# VoltageInput.net
KiCad netlist of a schematic drawn in Altium Designer
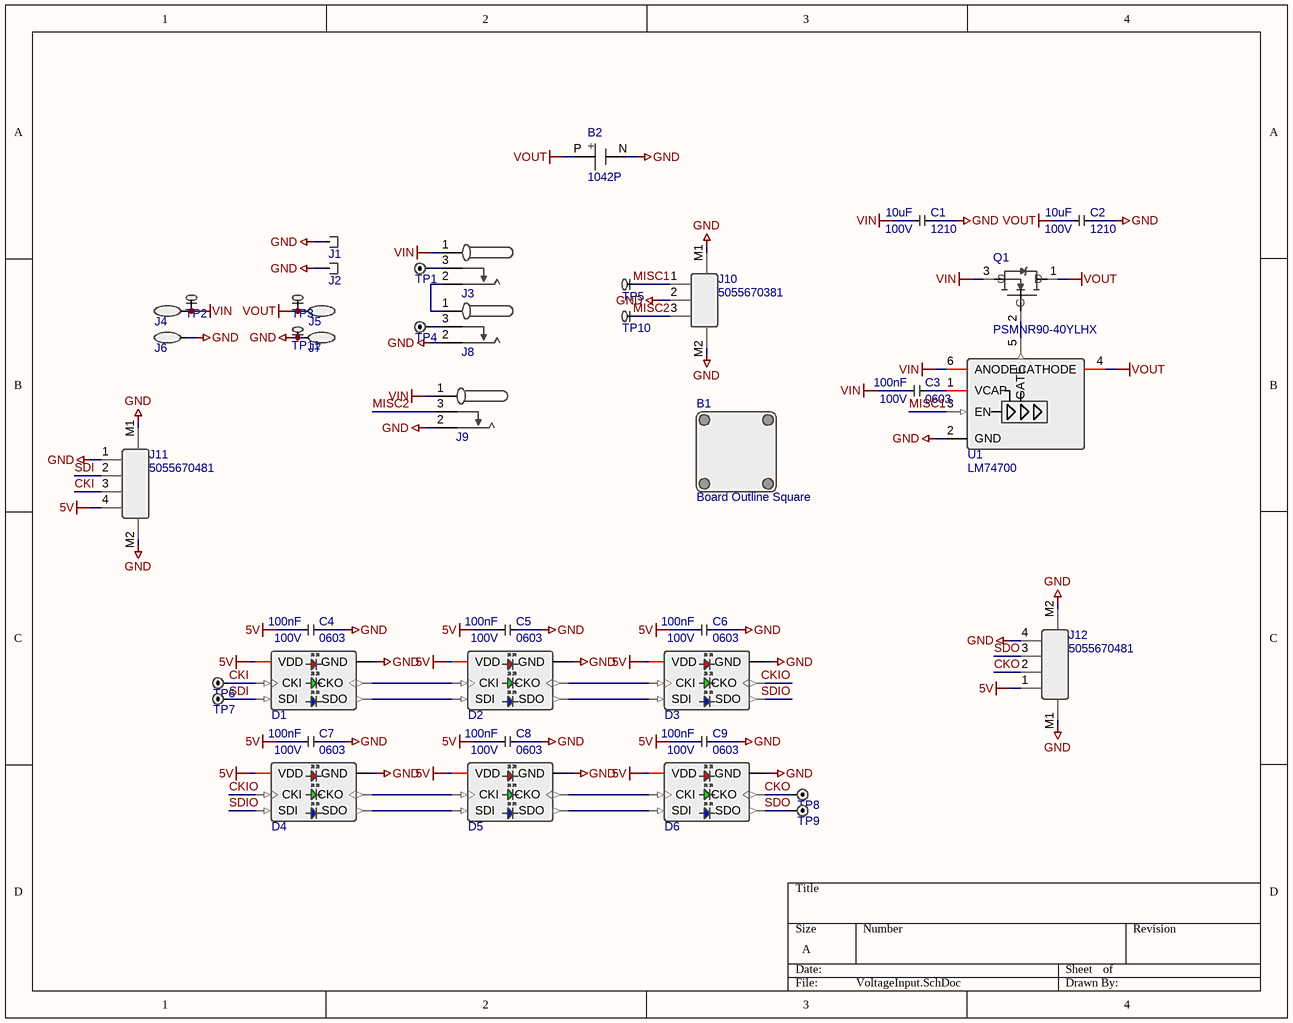
[diagram p0: VoltageInput.SchDoc]

(export (version "E")
  (design (tool "Eeschema 10.0.6"))
  (components
    (comp (ref "B1")
      (value "Board Outline Square")
      (footprint "PCB_OUTLINE_SQUARE")
      (libsource (lib "EE490") (part "Board_Outline_Square"))
    )
    (comp (ref "B2") (value "1042P") (libsource (lib "EE490") (part "Battery - Holder - Keystone 1042P")))
    (comp (ref "C1")
      (value "10uF")
      (footprint "CAPACITOR_1210(3225)_GENERIC")
      (description "10uF ±20% 100V Ceramic Capacitor X7S 1210(3225 Metric)")
      (fields
        (field (name "VOLTAGE - RATED") "100V")
        (field (name "PACKAGE/CASE IMPERIAL") "1210")
        (field (name "TOLERANCE") "20%")
        (field (name "Comment") "Capacitor - Ceramic - Generic")
      )
      (libsource (lib "EE490") (part "Capacitor - Ceramic - Generic"))
    )
    (comp (ref "C2")
      (value "10uF")
      (footprint "CAPACITOR_1210(3225)_GENERIC")
      (description "10uF ±20% 100V Ceramic Capacitor X7S 1210(3225 Metric)")
      (fields
        (field (name "VOLTAGE - RATED") "100V")
        (field (name "PACKAGE/CASE IMPERIAL") "1210")
        (field (name "TOLERANCE") "20%")
        (field (name "Comment") "Capacitor - Ceramic - Generic")
      )
      (libsource (lib "EE490") (part "Capacitor - Ceramic - Generic"))
    )
    (comp (ref "C3")
      (value "100nF")
      (footprint "CAPACITOR_0603(1608)_GENERIC")
      (description "100nF ±20% 100V Ceramic Capacitor X7R 0603(1608 Metric)")
      (fields
        (field (name "VOLTAGE - RATED") "100V")
        (field (name "PACKAGE/CASE IMPERIAL") "0603")
        (field (name "TOLERANCE") "20%")
        (field (name "Comment") "Capacitor - Ceramic - Generic")
      )
      (libsource (lib "EE490") (part "Capacitor - Ceramic - Generic"))
    )
    (comp (ref "C4")
      (value "100nF")
      (footprint "CAPACITOR_0603(1608)_GENERIC")
      (description "100nF ±20% 100V Ceramic Capacitor X7R 0603(1608 Metric)")
      (fields
        (field (name "VOLTAGE - RATED") "100V")
        (field (name "PACKAGE/CASE IMPERIAL") "0603")
        (field (name "TOLERANCE") "20%")
        (field (name "Comment") "Capacitor - Ceramic - Generic")
      )
      (libsource (lib "EE490") (part "Capacitor - Ceramic - Generic"))
    )
    (comp (ref "C5")
      (value "100nF")
      (footprint "CAPACITOR_0603(1608)_GENERIC")
      (description "100nF ±20% 100V Ceramic Capacitor X7R 0603(1608 Metric)")
      (fields
        (field (name "VOLTAGE - RATED") "100V")
        (field (name "PACKAGE/CASE IMPERIAL") "0603")
        (field (name "TOLERANCE") "20%")
        (field (name "Comment") "Capacitor - Ceramic - Generic")
      )
      (libsource (lib "EE490") (part "Capacitor - Ceramic - Generic"))
    )
    (comp (ref "C6")
      (value "100nF")
      (footprint "CAPACITOR_0603(1608)_GENERIC")
      (description "100nF ±20% 100V Ceramic Capacitor X7R 0603(1608 Metric)")
      (fields
        (field (name "VOLTAGE - RATED") "100V")
        (field (name "PACKAGE/CASE IMPERIAL") "0603")
        (field (name "TOLERANCE") "20%")
        (field (name "Comment") "Capacitor - Ceramic - Generic")
      )
      (libsource (lib "EE490") (part "Capacitor - Ceramic - Generic"))
    )
    (comp (ref "C7")
      (value "100nF")
      (footprint "CAPACITOR_0603(1608)_GENERIC")
      (description "100nF ±20% 100V Ceramic Capacitor X7R 0603(1608 Metric)")
      (fields
        (field (name "VOLTAGE - RATED") "100V")
        (field (name "PACKAGE/CASE IMPERIAL") "0603")
        (field (name "TOLERANCE") "20%")
        (field (name "Comment") "Capacitor - Ceramic - Generic")
      )
      (libsource (lib "EE490") (part "Capacitor - Ceramic - Generic"))
    )
    (comp (ref "C8")
      (value "100nF")
      (footprint "CAPACITOR_0603(1608)_GENERIC")
      (description "100nF ±20% 100V Ceramic Capacitor X7R 0603(1608 Metric)")
      (fields
        (field (name "VOLTAGE - RATED") "100V")
        (field (name "PACKAGE/CASE IMPERIAL") "0603")
        (field (name "TOLERANCE") "20%")
        (field (name "Comment") "Capacitor - Ceramic - Generic")
      )
      (libsource (lib "EE490") (part "Capacitor - Ceramic - Generic"))
    )
    (comp (ref "C9")
      (value "100nF")
      (footprint "CAPACITOR_0603(1608)_GENERIC")
      (description "100nF ±20% 100V Ceramic Capacitor X7R 0603(1608 Metric)")
      (fields
        (field (name "VOLTAGE - RATED") "100V")
        (field (name "PACKAGE/CASE IMPERIAL") "0603")
        (field (name "TOLERANCE") "20%")
        (field (name "Comment") "Capacitor - Ceramic - Generic")
      )
      (libsource (lib "EE490") (part "Capacitor - Ceramic - Generic"))
    )
    (comp (ref "D1")
      (value "APA102C")
      (footprint "5X5MM(6PIN)_JLEAD_GENERIC")
      (libsource (lib "EE490") (part "Diode - LED - Addressable - 5x5mm APA102C"))
    )
    (comp (ref "D2")
      (value "APA102C")
      (footprint "5X5MM(6PIN)_JLEAD_GENERIC")
      (libsource (lib "EE490") (part "Diode - LED - Addressable - 5x5mm APA102C"))
    )
    (comp (ref "D3")
      (value "APA102C")
      (footprint "5X5MM(6PIN)_JLEAD_GENERIC")
      (libsource (lib "EE490") (part "Diode - LED - Addressable - 5x5mm APA102C"))
    )
    (comp (ref "D4")
      (value "APA102C")
      (footprint "5X5MM(6PIN)_JLEAD_GENERIC")
      (libsource (lib "EE490") (part "Diode - LED - Addressable - 5x5mm APA102C"))
    )
    (comp (ref "D5")
      (value "APA102C")
      (footprint "5X5MM(6PIN)_JLEAD_GENERIC")
      (libsource (lib "EE490") (part "Diode - LED - Addressable - 5x5mm APA102C"))
    )
    (comp (ref "D6")
      (value "APA102C")
      (footprint "5X5MM(6PIN)_JLEAD_GENERIC")
      (libsource (lib "EE490") (part "Diode - LED - Addressable - 5x5mm APA102C"))
    )
    (comp (ref "J1")
      (value "PP45 Staple")
      (footprint "CONNECTOR_ACCESSORY_PP45-STAPLE_ANDERSON")
      (libsource (lib "EE490") (part "Connector - Accessory - Mechanical Support - Anderson PP45 Staple"))
    )
    (comp (ref "J2")
      (value "PP45 Staple")
      (footprint "CONNECTOR_ACCESSORY_PP45-STAPLE_ANDERSON")
      (libsource (lib "EE490") (part "Connector - Accessory - Mechanical Support - Anderson PP45 Staple"))
    )
    (comp (ref "J3")
      (value "839-1508-ND")
      (footprint "CONNECTOR_BARREL_TENSILITY_839-1508-ND")
      (libsource (lib "EE490") (part "Connector - Barrel - 3.5mmx1.1mm - Tensility 839-1508-ND"))
    )
    (comp (ref "J4")
      (value "PP45")
      (footprint "CONNECTOR_BTOC_PP45_ANDERSON")
      (libsource (lib "EE490") (part "Connector - Modular - 1P - Anderson PP45"))
    )
    (comp (ref "J5")
      (value "PP45")
      (footprint "CONNECTOR_BTOC_PP45_ANDERSON")
      (libsource (lib "EE490") (part "Connector - Modular - 1P - Anderson PP45"))
    )
    (comp (ref "J6")
      (value "PP45")
      (footprint "CONNECTOR_BTOC_PP45_ANDERSON")
      (libsource (lib "EE490") (part "Connector - Modular - 1P - Anderson PP45"))
    )
    (comp (ref "J7")
      (value "PP45")
      (footprint "CONNECTOR_BTOC_PP45_ANDERSON")
      (libsource (lib "EE490") (part "Connector - Modular - 1P - Anderson PP45"))
    )
    (comp (ref "J8")
      (value "839-1508-ND")
      (footprint "CONNECTOR_BARREL_TENSILITY_839-1508-ND")
      (libsource (lib "EE490") (part "Connector - Barrel - 3.5mmx1.1mm - Tensility 839-1508-ND"))
    )
    (comp (ref "J9")
      (value "839-1508-ND")
      (footprint "CONNECTOR_BARREL_TENSILITY_839-1508-ND")
      (libsource (lib "EE490") (part "Connector - Barrel - 3.5mmx1.1mm - Tensility 839-1508-ND"))
    )
    (comp (ref "J10")
      (value "Connector - Header - 3P 2M - Generic")
      (footprint "CONNECTOR_HEADER_MOLEX_5055670381")
      (description "Connector Header 3 Pin 1.25mm Pitch Mating 50V 2.4A Rated 5 Walls Shrouded SMT Molex 5055670381")
      (fields (field (name "MANUFACTURER PART NUMBER 1") "5055670381"))
      (libsource (lib "EE490") (part "Connector - Header - 3P 2M - Generic"))
    )
    (comp (ref "J11")
      (value "Connector - Header - 4P 2M - Generic")
      (footprint "CONNECTOR_HEADER_MOLEX_5055670481")
      (description "Connector Header 4 Pin 1.25mm Pitch Mating 50V 2.4A Rated 6 Walls Shrouded SMT Molex 5055670481")
      (fields (field (name "MANUFACTURER PART NUMBER 1") "5055670481"))
      (libsource (lib "EE490") (part "Connector - Header - 4P 2M - Generic"))
    )
    (comp (ref "J12")
      (value "Connector - Header - 4P 2M - Generic")
      (footprint "CONNECTOR_HEADER_MOLEX_5055670481")
      (description "Connector Header 4 Pin 1.25mm Pitch Mating 50V 2.4A Rated 6 Walls Shrouded SMT Molex 5055670481")
      (fields (field (name "MANUFACTURER PART NUMBER 1") "5055670481"))
      (libsource (lib "EE490") (part "Connector - Header - 4P 2M - Generic"))
    )
    (comp (ref "Q1")
      (value "PSMNR90-40YLHX")
      (footprint "SOT1023(LFPAK56E)_NEXPERIA")
      (libsource (lib "EE490") (part "MOSFET - N Channel - Nexperia PSMNR90-40YLHX"))
    )
    (comp (ref "TP1")
      (value "Test Point - THT")
      (footprint "TESTPOINT_THT_OCTAGON")
      (libsource (lib "EE490") (part "Test Point - THT"))
    )
    (comp (ref "TP2")
      (value "519XTR")
      (footprint "TESTPOINT_LOOP_SMD_KEYSTONE_519X")
      (libsource (lib "EE490") (part "Test Point - SMT - Loop - Keystone 519X"))
    )
    (comp (ref "TP3")
      (value "519XTR")
      (footprint "TESTPOINT_LOOP_SMD_KEYSTONE_519X")
      (libsource (lib "EE490") (part "Test Point - SMT - Loop - Keystone 519X"))
    )
    (comp (ref "TP4")
      (value "Test Point - THT")
      (footprint "TESTPOINT_THT_OCTAGON")
      (libsource (lib "EE490") (part "Test Point - THT"))
    )
    (comp (ref "TP5")
      (value "519XTR")
      (footprint "TESTPOINT_LOOP_SMD_KEYSTONE_519X")
      (libsource (lib "EE490") (part "Test Point - SMT - Loop - Keystone 519X"))
    )
    (comp (ref "TP6")
      (value "Test Point - THT")
      (footprint "TESTPOINT_THT_OCTAGON")
      (libsource (lib "EE490") (part "Test Point - THT"))
    )
    (comp (ref "TP7")
      (value "Test Point - THT")
      (footprint "TESTPOINT_THT_OCTAGON")
      (libsource (lib "EE490") (part "Test Point - THT"))
    )
    (comp (ref "TP8")
      (value "Test Point - THT")
      (footprint "TESTPOINT_THT_OCTAGON")
      (libsource (lib "EE490") (part "Test Point - THT"))
    )
    (comp (ref "TP9")
      (value "Test Point - THT")
      (footprint "TESTPOINT_THT_OCTAGON")
      (libsource (lib "EE490") (part "Test Point - THT"))
    )
    (comp (ref "TP10")
      (value "519XTR")
      (footprint "TESTPOINT_LOOP_SMD_KEYSTONE_519X")
      (libsource (lib "EE490") (part "Test Point - SMT - Loop - Keystone 519X"))
    )
    (comp (ref "TP11")
      (value "519XTR")
      (footprint "TESTPOINT_LOOP_SMD_KEYSTONE_519X")
      (libsource (lib "EE490") (part "Test Point - SMT - Loop - Keystone 519X"))
    )
    (comp (ref "U1")
      (value "LM74700")
      (footprint "SOT23-6(DBV0006A)_TI")
      (libsource (lib "EE490") (part "IC - Power Management - Ideal Diode Controller - TI LM74700"))
    )
  )
  (nets
    (net (code "1") (name "/CKI") (class "Default")
      (node (ref "D1") (pin "2") (pinfunction "CKI_2") (pintype "input"))
      (node (ref "J11") (pin "3") (pinfunction "0_3") (pintype "passive"))
      (node (ref "TP6") (pin "1") (pinfunction "1_1") (pintype "passive"))
    )
    (net (code "2") (name "/CKIO") (class "Default")
      (node (ref "D3") (pin "5") (pinfunction "CKO_5") (pintype "output"))
      (node (ref "D4") (pin "2") (pinfunction "CKI_2") (pintype "input"))
    )
    (net (code "3") (name "/CKO") (class "Default")
      (node (ref "D6") (pin "5") (pinfunction "CKO_5") (pintype "output"))
      (node (ref "J12") (pin "2") (pinfunction "0_2") (pintype "passive"))
      (node (ref "TP8") (pin "1") (pinfunction "1_1") (pintype "passive"))
    )
    (net (code "4") (name "/MISC1") (class "Default")
      (node (ref "J10") (pin "1") (pinfunction "0_1") (pintype "passive"))
      (node (ref "TP5") (pin "1") (pinfunction "1_1") (pintype "passive"))
      (node (ref "U1") (pin "3") (pinfunction "EN_3") (pintype "input"))
    )
    (net (code "5") (name "/MISC2") (class "Default")
      (node (ref "J10") (pin "3") (pinfunction "0_3") (pintype "passive"))
      (node (ref "J9") (pin "3") (pinfunction "3_3") (pintype "passive"))
      (node (ref "TP10") (pin "1") (pinfunction "1_1") (pintype "passive"))
    )
    (net (code "6") (name "/SDI") (class "Default")
      (node (ref "D1") (pin "1") (pinfunction "SDI_1") (pintype "input"))
      (node (ref "J11") (pin "2") (pinfunction "0_2") (pintype "passive"))
      (node (ref "TP7") (pin "1") (pinfunction "1_1") (pintype "passive"))
    )
    (net (code "7") (name "/SDIO") (class "Default")
      (node (ref "D3") (pin "6") (pinfunction "SDO_6") (pintype "output"))
      (node (ref "D4") (pin "1") (pinfunction "SDI_1") (pintype "input"))
    )
    (net (code "8") (name "/SDO") (class "Default")
      (node (ref "D6") (pin "6") (pinfunction "SDO_6") (pintype "output"))
      (node (ref "J12") (pin "3") (pinfunction "0_3") (pintype "passive"))
      (node (ref "TP9") (pin "1") (pinfunction "1_1") (pintype "passive"))
    )
    (net (code "9") (name "5V") (class "Default")
      (node (ref "C4") (pin "1") (pinfunction "1_1") (pintype "passive"))
      (node (ref "C5") (pin "1") (pinfunction "1_1") (pintype "passive"))
      (node (ref "C6") (pin "1") (pinfunction "1_1") (pintype "passive"))
      (node (ref "C7") (pin "1") (pinfunction "1_1") (pintype "passive"))
      (node (ref "C8") (pin "1") (pinfunction "1_1") (pintype "passive"))
      (node (ref "C9") (pin "1") (pinfunction "1_1") (pintype "passive"))
      (node (ref "D1") (pin "4") (pinfunction "VDD_4") (pintype "power_in"))
      (node (ref "D2") (pin "4") (pinfunction "VDD_4") (pintype "power_in"))
      (node (ref "D3") (pin "4") (pinfunction "VDD_4") (pintype "power_in"))
      (node (ref "D4") (pin "4") (pinfunction "VDD_4") (pintype "power_in"))
      (node (ref "D5") (pin "4") (pinfunction "VDD_4") (pintype "power_in"))
      (node (ref "D6") (pin "4") (pinfunction "VDD_4") (pintype "power_in"))
      (node (ref "J11") (pin "4") (pinfunction "0_4") (pintype "passive"))
      (node (ref "J12") (pin "1") (pinfunction "0_1") (pintype "passive"))
    )
    (net (code "10") (name "GND") (class "Default")
      (node (ref "B2") (pin "N") (pinfunction "N_N") (pintype "passive"))
      (node (ref "C1") (pin "2") (pinfunction "2_2") (pintype "passive"))
      (node (ref "C2") (pin "2") (pinfunction "2_2") (pintype "passive"))
      (node (ref "C4") (pin "2") (pinfunction "2_2") (pintype "passive"))
      (node (ref "C5") (pin "2") (pinfunction "2_2") (pintype "passive"))
      (node (ref "C6") (pin "2") (pinfunction "2_2") (pintype "passive"))
      (node (ref "C7") (pin "2") (pinfunction "2_2") (pintype "passive"))
      (node (ref "C8") (pin "2") (pinfunction "2_2") (pintype "passive"))
      (node (ref "C9") (pin "2") (pinfunction "2_2") (pintype "passive"))
      (node (ref "D1") (pin "3") (pinfunction "GND_3") (pintype "power_in"))
      (node (ref "D2") (pin "3") (pinfunction "GND_3") (pintype "power_in"))
      (node (ref "D3") (pin "3") (pinfunction "GND_3") (pintype "power_in"))
      (node (ref "D4") (pin "3") (pinfunction "GND_3") (pintype "power_in"))
      (node (ref "D5") (pin "3") (pinfunction "GND_3") (pintype "power_in"))
      (node (ref "D6") (pin "3") (pinfunction "GND_3") (pintype "power_in"))
      (node (ref "J1") (pin "1") (pinfunction "1_1") (pintype "passive"))
      (node (ref "J10") (pin "2") (pinfunction "0_2") (pintype "passive"))
      (node (ref "J10") (pin "M1") (pinfunction "1_M1") (pintype "passive"))
      (node (ref "J10") (pin "M2") (pinfunction "1_M2") (pintype "passive"))
      (node (ref "J11") (pin "1") (pinfunction "0_1") (pintype "passive"))
      (node (ref "J11") (pin "M1") (pinfunction "1_M1") (pintype "passive"))
      (node (ref "J11") (pin "M2") (pinfunction "1_M2") (pintype "passive"))
      (node (ref "J12") (pin "4") (pinfunction "0_4") (pintype "passive"))
      (node (ref "J12") (pin "M1") (pinfunction "1_M1") (pintype "passive"))
      (node (ref "J12") (pin "M2") (pinfunction "1_M2") (pintype "passive"))
      (node (ref "J2") (pin "1") (pinfunction "1_1") (pintype "passive"))
      (node (ref "J6") (pin "1") (pinfunction "1_1") (pintype "passive"))
      (node (ref "J7") (pin "1") (pinfunction "1_1") (pintype "passive"))
      (node (ref "J8") (pin "2") (pinfunction "2_2") (pintype "passive"))
      (node (ref "J9") (pin "2") (pinfunction "2_2") (pintype "passive"))
      (node (ref "TP11") (pin "1") (pinfunction "1_1") (pintype "passive"))
      (node (ref "U1") (pin "2") (pinfunction "GND_2") (pintype "power_in"))
    )
    (net (code "11") (name "Net-(D1-CKO)") (class "Default")
      (node (ref "D1") (pin "5") (pinfunction "CKO_5") (pintype "output"))
      (node (ref "D2") (pin "2") (pinfunction "CKI_2") (pintype "input"))
    )
    (net (code "12") (name "Net-(D1-SDO)") (class "Default")
      (node (ref "D1") (pin "6") (pinfunction "SDO_6") (pintype "output"))
      (node (ref "D2") (pin "1") (pinfunction "SDI_1") (pintype "input"))
    )
    (net (code "13") (name "Net-(D2-CKO)") (class "Default")
      (node (ref "D2") (pin "5") (pinfunction "CKO_5") (pintype "output"))
      (node (ref "D3") (pin "2") (pinfunction "CKI_2") (pintype "input"))
    )
    (net (code "14") (name "Net-(D2-SDO)") (class "Default")
      (node (ref "D2") (pin "6") (pinfunction "SDO_6") (pintype "output"))
      (node (ref "D3") (pin "1") (pinfunction "SDI_1") (pintype "input"))
    )
    (net (code "15") (name "Net-(D4-CKO)") (class "Default")
      (node (ref "D4") (pin "5") (pinfunction "CKO_5") (pintype "output"))
      (node (ref "D5") (pin "2") (pinfunction "CKI_2") (pintype "input"))
    )
    (net (code "16") (name "Net-(D4-SDO)") (class "Default")
      (node (ref "D4") (pin "6") (pinfunction "SDO_6") (pintype "output"))
      (node (ref "D5") (pin "1") (pinfunction "SDI_1") (pintype "input"))
    )
    (net (code "17") (name "Net-(D5-CKO)") (class "Default")
      (node (ref "D5") (pin "5") (pinfunction "CKO_5") (pintype "output"))
      (node (ref "D6") (pin "2") (pinfunction "CKI_2") (pintype "input"))
    )
    (net (code "18") (name "Net-(D5-SDO)") (class "Default")
      (node (ref "D5") (pin "6") (pinfunction "SDO_6") (pintype "output"))
      (node (ref "D6") (pin "1") (pinfunction "SDI_1") (pintype "input"))
    )
    (net (code "19") (name "Net-(J3-Pad2)") (class "Default")
      (node (ref "J3") (pin "2") (pinfunction "2_2") (pintype "passive"))
      (node (ref "J8") (pin "1") (pinfunction "1_1") (pintype "passive"))
    )
    (net (code "20") (name "Net-(J3-Pad3)") (class "Default")
      (node (ref "J3") (pin "3") (pinfunction "3_3") (pintype "passive"))
      (node (ref "TP1") (pin "1") (pinfunction "1_1") (pintype "passive"))
    )
    (net (code "21") (name "Net-(J8-Pad3)") (class "Default")
      (node (ref "J8") (pin "3") (pinfunction "3_3") (pintype "passive"))
      (node (ref "TP4") (pin "1") (pinfunction "1_1") (pintype "passive"))
    )
    (net (code "22") (name "Net-(Q1-G)") (class "Default")
      (node (ref "Q1") (pin "2") (pinfunction "G_2") (pintype "passive"))
      (node (ref "U1") (pin "5") (pinfunction "GATE_5") (pintype "output"))
    )
    (net (code "23") (name "Net-(U1-VCAP)") (class "Default")
      (node (ref "C3") (pin "2") (pinfunction "2_2") (pintype "passive"))
      (node (ref "U1") (pin "1") (pinfunction "VCAP_1") (pintype "power_in"))
    )
    (net (code "24") (name "VIN") (class "Default")
      (node (ref "C1") (pin "1") (pinfunction "1_1") (pintype "passive"))
      (node (ref "C3") (pin "1") (pinfunction "1_1") (pintype "passive"))
      (node (ref "J3") (pin "1") (pinfunction "1_1") (pintype "passive"))
      (node (ref "J4") (pin "1") (pinfunction "1_1") (pintype "passive"))
      (node (ref "J9") (pin "1") (pinfunction "1_1") (pintype "passive"))
      (node (ref "Q1") (pin "3") (pinfunction "S_3") (pintype "power_in"))
      (node (ref "TP2") (pin "1") (pinfunction "1_1") (pintype "passive"))
      (node (ref "U1") (pin "6") (pinfunction "ANODE_6") (pintype "power_in"))
    )
    (net (code "25") (name "VOUT") (class "Default")
      (node (ref "B2") (pin "P") (pinfunction "P_P") (pintype "passive"))
      (node (ref "C2") (pin "1") (pinfunction "1_1") (pintype "passive"))
      (node (ref "J5") (pin "1") (pinfunction "1_1") (pintype "passive"))
      (node (ref "Q1") (pin "1") (pinfunction "D_1") (pintype "power_in"))
      (node (ref "TP3") (pin "1") (pinfunction "1_1") (pintype "passive"))
      (node (ref "U1") (pin "4") (pinfunction "CATHODE_4") (pintype "passive"))
    )
  )
)
